# RK3562-VCCIO4.net
KiCad netlist of a schematic drawn in Altium Designer
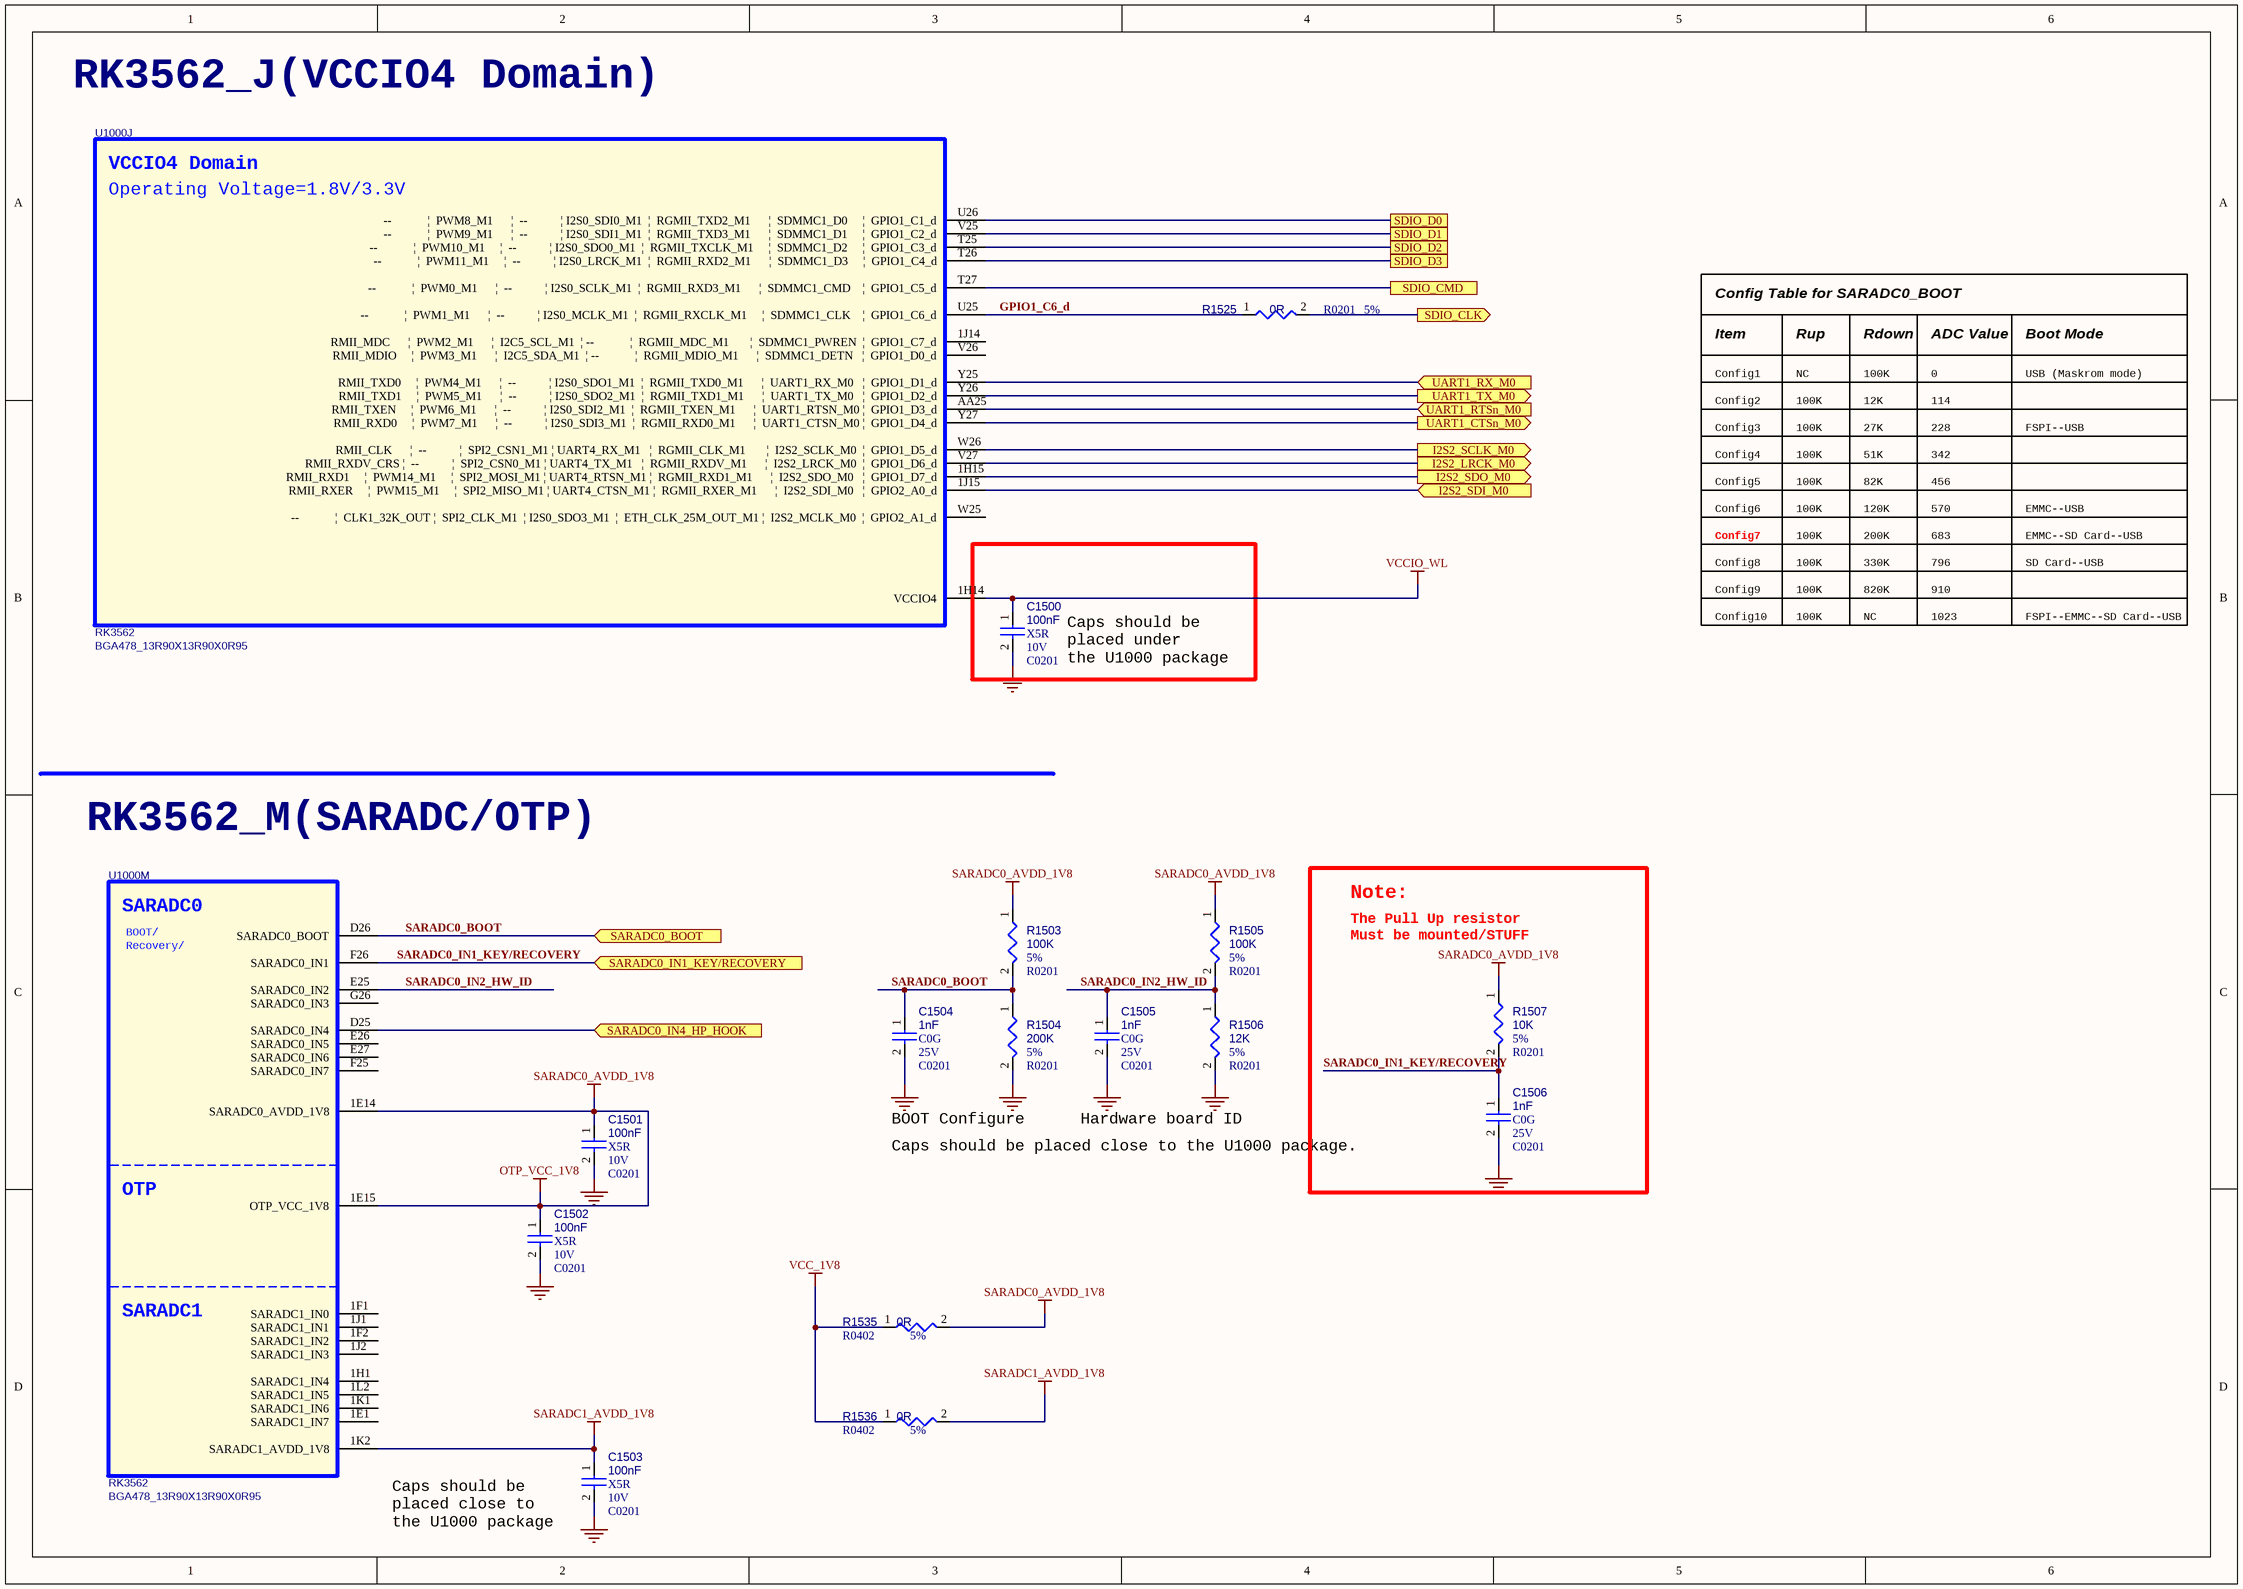
[diagram p0: RK3562-VCCIO4.SchDoc]

(export (version "E")
  (design (tool "Eeschema 10.0.6"))
  (components
    (comp (ref "C1500")
      (value "100nF")
      (footprint "C0201")
      (description "cap,100.00nF,+/-10%,10V,X5R,C0201")
      (fields
        (field (name "DIELECTRIC") "X5R")
        (field (name "PCB FOOTPRINT") "C0201")
        (field (name "VOLTAGE") "10V")
        (field (name "TOLERANCE") "10%")
        (field (name "MANUFACTURER") "TDK")
        (field (name "CREATED BY") "JJJ")
      )
      (libsource (lib "RK3562_REF") (part "CAP NP"))
    )
    (comp (ref "C1501")
      (value "100nF")
      (footprint "C0201")
      (description "cap,100.00nF,+/-10%,10V,X5R,C0201")
      (fields
        (field (name "DIELECTRIC") "X5R")
        (field (name "PCB FOOTPRINT") "C0201")
        (field (name "VOLTAGE") "10V")
        (field (name "TOLERANCE") "10%")
        (field (name "MANUFACTURER") "TDK")
        (field (name "CREATED BY") "JJJ")
      )
      (libsource (lib "RK3562_REF") (part "CAP NP"))
    )
    (comp (ref "C1502")
      (value "100nF")
      (footprint "C0201")
      (description "cap,100.00nF,+/-10%,10V,X5R,C0201")
      (fields
        (field (name "DIELECTRIC") "X5R")
        (field (name "PCB FOOTPRINT") "C0201")
        (field (name "VOLTAGE") "10V")
        (field (name "MANUFACTURER") "TDK")
        (field (name "TOLERANCE") "10%")
        (field (name "CREATED BY") "JJJ")
      )
      (libsource (lib "RK3562_REF") (part "CAP NP"))
    )
    (comp (ref "C1503")
      (value "100nF")
      (footprint "C0201")
      (description "cap,100.00nF,+/-10%,10V,X5R,C0201")
      (fields
        (field (name "DIELECTRIC") "X5R")
        (field (name "PCB FOOTPRINT") "C0201")
        (field (name "VOLTAGE") "10V")
        (field (name "TOLERANCE") "10%")
        (field (name "MANUFACTURER") "TDK")
        (field (name "CREATED BY") "JJJ")
      )
      (libsource (lib "RK3562_REF") (part "CAP NP"))
    )
    (comp (ref "C1504")
      (value "1nF")
      (footprint "C0201")
      (description "一般用片状陶瓷电容(GRM),cap,1nF,±5%,25V,C0G,C0201")
      (fields
        (field (name "DIELECTRIC") "C0G")
        (field (name "PCB FOOTPRINT") "C0201")
        (field (name "VOLTAGE") "25V")
        (field (name "MANUFACTURER") "murata")
        (field (name "TOLERANCE") "±5%")
        (field (name "CREATED BY") "JJJ")
      )
      (libsource (lib "RK3562_REF") (part "CAP NP"))
    )
    (comp (ref "C1505")
      (value "1nF")
      (footprint "C0201")
      (description "一般用片状陶瓷电容(GRM),cap,1nF,±5%,25V,C0G,C0201")
      (fields
        (field (name "DIELECTRIC") "C0G")
        (field (name "PCB FOOTPRINT") "C0201")
        (field (name "VOLTAGE") "25V")
        (field (name "TOLERANCE") "±5%")
        (field (name "MANUFACTURER") "murata")
        (field (name "CREATED BY") "JJJ")
      )
      (libsource (lib "RK3562_REF") (part "CAP NP"))
    )
    (comp (ref "C1506")
      (value "1nF")
      (footprint "C0201")
      (description "一般用片状陶瓷电容(GRM),cap,1nF,±5%,25V,C0G,C0201")
      (fields
        (field (name "DIELECTRIC") "C0G")
        (field (name "PCB FOOTPRINT") "C0201")
        (field (name "VOLTAGE") "25V")
        (field (name "TOLERANCE") "±5%")
        (field (name "MANUFACTURER") "murata")
        (field (name "CREATED BY") "JJJ")
      )
      (libsource (lib "RK3562_REF") (part "CAP NP"))
    )
    (comp (ref "R1503")
      (value "100K")
      (footprint "R0201")
      (description "通用厚膜电阻,100K,+/-5%,R0201,1/20W.")
      (fields
        (field (name "TOLERANCE") "5%")
        (field (name "PCB FOOTPRINT") "R0201")
        (field (name "MANUFACTURER") "YAGEO")
        (field (name "CREATED BY") "YTL")
      )
      (libsource (lib "RK3562_REF") (part "RESISTOR"))
    )
    (comp (ref "R1504")
      (value "200K")
      (footprint "R0201")
      (description "通用厚膜电阻,200K,+/-5%,R0201,1/20W.")
      (fields
        (field (name "TOLERANCE") "5%")
        (field (name "PCB FOOTPRINT") "R0201")
        (field (name "MANUFACTURER") "YAGEO")
        (field (name "CREATED BY") "YTL")
      )
      (libsource (lib "RK3562_REF") (part "RESISTOR"))
    )
    (comp (ref "R1505")
      (value "100K")
      (footprint "R0201")
      (description "通用厚膜电阻,100K,+/-5%,R0201,1/20W.")
      (fields
        (field (name "TOLERANCE") "5%")
        (field (name "PCB FOOTPRINT") "R0201")
        (field (name "MANUFACTURER") "YAGEO")
        (field (name "CREATED BY") "YTL")
      )
      (libsource (lib "RK3562_REF") (part "RESISTOR"))
    )
    (comp (ref "R1506")
      (value "12K")
      (footprint "R0201")
      (description "通用厚膜电阻,12K,+/-5%,R0201,1/20W.")
      (fields
        (field (name "TOLERANCE") "5%")
        (field (name "PCB FOOTPRINT") "R0201")
        (field (name "MANUFACTURER") "YAGEO")
        (field (name "CREATED BY") "YTL")
      )
      (libsource (lib "RK3562_REF") (part "RESISTOR"))
    )
    (comp (ref "R1507")
      (value "10K")
      (footprint "R0201")
      (description "通用厚膜电阻,10K,+/-5%,R0201,1/20W.")
      (fields
        (field (name "TOLERANCE") "5%")
        (field (name "PCB FOOTPRINT") "R0201")
        (field (name "MANUFACTURER") "YAGEO")
        (field (name "CREATED BY") "YTL")
      )
      (libsource (lib "RK3562_REF") (part "RESISTOR"))
    )
    (comp (ref "R1525")
      (value "0R")
      (footprint "R0201")
      (description "通用厚膜电阻,0R,+/-5%,R0201,1/20W.")
      (fields
        (field (name "TOLERANCE") "5%")
        (field (name "PCB FOOTPRINT") "R0201")
        (field (name "MANUFACTURER") "YAGEO")
        (field (name "CREATED BY") "YTL")
      )
      (libsource (lib "RK3562_REF") (part "RESISTOR"))
    )
    (comp (ref "R1535")
      (value "0R")
      (footprint "R0402")
      (description "通用厚膜电阻,0R,+/-5%,R0402,1/16W.")
      (fields
        (field (name "TOLERANCE") "5%")
        (field (name "PCB FOOTPRINT") "R0402")
        (field (name "MANUFACTURER") "YAGEO")
        (field (name "CREATED BY") "YTL")
      )
      (libsource (lib "RK3562_REF") (part "RESISTOR"))
    )
    (comp (ref "R1536")
      (value "0R")
      (footprint "R0402")
      (description "通用厚膜电阻,0R,+/-5%,R0402,1/16W.")
      (fields
        (field (name "TOLERANCE") "5%")
        (field (name "PCB FOOTPRINT") "R0402")
        (field (name "MANUFACTURER") "YAGEO")
        (field (name "CREATED BY") "YTL")
      )
      (libsource (lib "RK3562_REF") (part "RESISTOR"))
    )
    (comp (ref "U1000")
      (value "RK3562")
      (footprint "BGA478_13R90X13R90X0R95")
      (description "ROCKCHIP SOC")
      (fields
        (field (name "PCB FOOTPRINT") "BGA478_13R90X13R90X0R95")
        (field (name "MANUFACTURER") "Rockchip (瑞芯微)")
        (field (name "CREATED BY") "JJJ")
      )
      (libsource (lib "RK3562_REF") (part "SOC_RK3562"))
    )
  )
  (nets
    (net (code "1") (name "/GPIO1_C6_d") (class "Default")
      (node (ref "R1525") (pin "1") (pinfunction "1_1") (pintype "passive"))
      (node (ref "U1000") (pin "U25") (pinfunction "--____________¦__PWM1_M1______¦__--___________¦_I2S0_MCLK_M1__¦__RGMII_RXCLK_M1_____¦__SDMMC1_CLK____¦__GPIO1_C6_d_U25") (pintype "passive"))
    )
    (net (code "2") (name "/I2S2_LRCK_M0") (class "Default")
      (node (ref "U1000") (pin "V27") (pinfunction "RMII_RXDV_CRS_¦__--___________¦__SPI2_CSN0_M1_¦_UART4_TX_M1___¦__RGMII_RXDV_M1______¦__I2S2_LRCK_M0__¦__GPIO1_D6_d_V27") (pintype "passive"))
    )
    (net (code "3") (name "/I2S2_SCLK_M0") (class "Default")
      (node (ref "U1000") (pin "W26") (pinfunction "RMII_CLK______¦__--___________¦__SPI2_CSN1_M1_¦_UART4_RX_M1___¦__RGMII_CLK_M1_______¦__I2S2_SCLK_M0__¦__GPIO1_D5_d_W26") (pintype "passive"))
    )
    (net (code "4") (name "/I2S2_SDI_M0") (class "Default")
      (node (ref "U1000") (pin "1J15") (pinfunction "RMII_RXER_____¦__PWM15_M1_____¦__SPI2_MISO_M1_¦_UART4_CTSN_M1_¦__RGMII_RXER_M1______¦__I2S2_SDI_M0___¦__GPIO2_A0_d_1J15") (pintype "passive"))
    )
    (net (code "5") (name "/I2S2_SDO_M0") (class "Default")
      (node (ref "U1000") (pin "1H15") (pinfunction "RMII_RXD1_____¦__PWM14_M1_____¦__SPI2_MOSI_M1_¦_UART4_RTSN_M1_¦__RGMII_RXD1_M1______¦__I2S2_SDO_M0___¦__GPIO1_D7_d_1H15") (pintype "passive"))
    )
    (net (code "6") (name "/SARADC0_BOOT") (class "Default")
      (node (ref "C1504") (pin "1") (pinfunction "1_1") (pintype "passive"))
      (node (ref "R1503") (pin "2") (pinfunction "2_2") (pintype "passive"))
      (node (ref "R1504") (pin "1") (pinfunction "1_1") (pintype "passive"))
      (node (ref "U1000") (pin "D26") (pinfunction "SARADC0_BOOT_D26") (pintype "passive"))
    )
    (net (code "7") (name "/SARADC0_IN1_KEY{slash}RECOVERY") (class "Default")
      (node (ref "C1506") (pin "1") (pinfunction "1_1") (pintype "passive"))
      (node (ref "R1507") (pin "2") (pinfunction "2_2") (pintype "passive"))
      (node (ref "U1000") (pin "F26") (pinfunction "SARADC0_IN1_F26") (pintype "passive"))
    )
    (net (code "8") (name "/SARADC0_IN2_HW_ID") (class "Default")
      (node (ref "C1505") (pin "1") (pinfunction "1_1") (pintype "passive"))
      (node (ref "R1505") (pin "2") (pinfunction "2_2") (pintype "passive"))
      (node (ref "R1506") (pin "1") (pinfunction "1_1") (pintype "passive"))
      (node (ref "U1000") (pin "E25") (pinfunction "SARADC0_IN2_E25") (pintype "passive"))
    )
    (net (code "9") (name "/SARADC0_IN4_HP_HOOK") (class "Default")
      (node (ref "U1000") (pin "D25") (pinfunction "SARADC0_IN4_D25") (pintype "passive"))
    )
    (net (code "10") (name "/SDIO_CLK") (class "Default")
      (node (ref "R1525") (pin "2") (pinfunction "2_2") (pintype "passive"))
    )
    (net (code "11") (name "/SDIO_CMD") (class "Default")
      (node (ref "U1000") (pin "T27") (pinfunction "--____________¦__PWM0_M1______¦__--___________¦_I2S0_SCLK_M1__¦__RGMII_RXD3_M1______¦__SDMMC1_CMD____¦__GPIO1_C5_d_T27") (pintype "passive"))
    )
    (net (code "12") (name "/SDIO_D0") (class "Default")
      (node (ref "U1000") (pin "U26") (pinfunction "--____________¦__PWM8_M1______¦__--___________¦_I2S0_SDI0_M1__¦__RGMII_TXD2_M1______¦__SDMMC1_D0_____¦__GPIO1_C1_d_U26") (pintype "passive"))
    )
    (net (code "13") (name "/SDIO_D1") (class "Default")
      (node (ref "U1000") (pin "V25") (pinfunction "--____________¦__PWM9_M1______¦__--___________¦_I2S0_SDI1_M1__¦__RGMII_TXD3_M1______¦__SDMMC1_D1_____¦__GPIO1_C2_d_V25") (pintype "passive"))
    )
    (net (code "14") (name "/SDIO_D2") (class "Default")
      (node (ref "U1000") (pin "T25") (pinfunction "--____________¦__PWM10_M1_____¦__--___________¦_I2S0_SDO0_M1__¦__RGMII_TXCLK_M1_____¦__SDMMC1_D2_____¦__GPIO1_C3_d_T25") (pintype "passive"))
    )
    (net (code "15") (name "/SDIO_D3") (class "Default")
      (node (ref "U1000") (pin "T26") (pinfunction "--____________¦__PWM11_M1_____¦__--___________¦_I2S0_LRCK_M1__¦__RGMII_RXD2_M1______¦__SDMMC1_D3_____¦__GPIO1_C4_d_T26") (pintype "passive"))
    )
    (net (code "16") (name "/UART1_CTSn_M0") (class "Default")
      (node (ref "U1000") (pin "Y27") (pinfunction "RMII_RXD0_____¦__PWM7_M1______¦__--___________¦_I2S0_SDI3_M1__¦__RGMII_RXD0_M1______¦__UART1_CTSN_M0_¦__GPIO1_D4_d_Y27") (pintype "passive"))
    )
    (net (code "17") (name "/UART1_RTSn_M0") (class "Default")
      (node (ref "U1000") (pin "AA25") (pinfunction "RMII_TXEN_____¦__PWM6_M1______¦__--___________¦_I2S0_SDI2_M1__¦__RGMII_TXEN_M1______¦__UART1_RTSN_M0_¦__GPIO1_D3_d_AA25") (pintype "passive"))
    )
    (net (code "18") (name "/UART1_RX_M0") (class "Default")
      (node (ref "U1000") (pin "Y25") (pinfunction "RMII_TXD0_____¦__PWM4_M1______¦__--___________¦_I2S0_SDO1_M1__¦__RGMII_TXD0_M1______¦__UART1_RX_M0___¦__GPIO1_D1_d_Y25") (pintype "passive"))
    )
    (net (code "19") (name "/UART1_TX_M0") (class "Default")
      (node (ref "U1000") (pin "Y26") (pinfunction "RMII_TXD1_____¦__PWM5_M1______¦__--___________¦_I2S0_SDO2_M1__¦__RGMII_TXD1_M1______¦__UART1_TX_M0___¦__GPIO1_D2_d_Y26") (pintype "passive"))
    )
    (net (code "20") (name "GND") (class "Default")
      (node (ref "C1500") (pin "2") (pinfunction "2_2") (pintype "passive"))
      (node (ref "C1501") (pin "2") (pinfunction "2_2") (pintype "passive"))
      (node (ref "C1502") (pin "2") (pinfunction "2_2") (pintype "passive"))
      (node (ref "C1503") (pin "2") (pinfunction "2_2") (pintype "passive"))
      (node (ref "C1504") (pin "2") (pinfunction "2_2") (pintype "passive"))
      (node (ref "C1505") (pin "2") (pinfunction "2_2") (pintype "passive"))
      (node (ref "C1506") (pin "2") (pinfunction "2_2") (pintype "passive"))
      (node (ref "R1504") (pin "2") (pinfunction "2_2") (pintype "passive"))
      (node (ref "R1506") (pin "2") (pinfunction "2_2") (pintype "passive"))
    )
    (net (code "21") (name "OTP_VCC_1V8") (class "Default")
      (node (ref "C1501") (pin "1") (pinfunction "1_1") (pintype "passive"))
      (node (ref "C1502") (pin "1") (pinfunction "1_1") (pintype "passive"))
      (node (ref "R1503") (pin "1") (pinfunction "1_1") (pintype "passive"))
      (node (ref "R1505") (pin "1") (pinfunction "1_1") (pintype "passive"))
      (node (ref "R1507") (pin "1") (pinfunction "1_1") (pintype "passive"))
      (node (ref "R1535") (pin "2") (pinfunction "2_2") (pintype "passive"))
      (node (ref "U1000") (pin "1E14") (pinfunction "SARADC0_AVDD_1V8_1E14") (pintype "passive"))
      (node (ref "U1000") (pin "1E15") (pinfunction "OTP_VCC_1V8_1E15") (pintype "passive"))
    )
    (net (code "22") (name "SARADC1_AVDD_1V8") (class "Default")
      (node (ref "C1503") (pin "1") (pinfunction "1_1") (pintype "passive"))
      (node (ref "R1536") (pin "2") (pinfunction "2_2") (pintype "passive"))
      (node (ref "U1000") (pin "1K2") (pinfunction "SARADC1_AVDD_1V8_1K2") (pintype "passive"))
    )
    (net (code "23") (name "VCCIO_WL") (class "Default")
      (node (ref "C1500") (pin "1") (pinfunction "1_1") (pintype "passive"))
      (node (ref "U1000") (pin "1H14") (pinfunction "VCCIO4_1H14") (pintype "passive"))
    )
    (net (code "24") (name "VCC_1V8") (class "Default")
      (node (ref "R1535") (pin "1") (pinfunction "1_1") (pintype "passive"))
      (node (ref "R1536") (pin "1") (pinfunction "1_1") (pintype "passive"))
    )
    (net (code "25") (name "unconnected-(U1000J---____________¦__CLK1_32K_OUT_¦__SPI2_CLK_M1__¦_I2S0_SDO3_M1__¦__ETH_CLK_25M_OUT_M1_¦__I2S2_MCLK_M0__¦__GPIO2_A1_d-PadW25)") (class "Default")
      (node (ref "U1000") (pin "W25") (pinfunction "--____________¦__CLK1_32K_OUT_¦__SPI2_CLK_M1__¦_I2S0_SDO3_M1__¦__ETH_CLK_25M_OUT_M1_¦__I2S2_MCLK_M0__¦__GPIO2_A1_d_W25") (pintype "passive"))
    )
    (net (code "26") (name "unconnected-(U1000J-RMII_MDC______¦__PWM2_M1______¦__I2C5_SCL_M1__¦_--____________¦__RGMII_MDC_M1_______¦__SDMMC1_PWREN__¦__GPIO1_C7_d-Pad1J14)") (class "Default")
      (node (ref "U1000") (pin "1J14") (pinfunction "RMII_MDC______¦__PWM2_M1______¦__I2C5_SCL_M1__¦_--____________¦__RGMII_MDC_M1_______¦__SDMMC1_PWREN__¦__GPIO1_C7_d_1J14") (pintype "passive"))
    )
    (net (code "27") (name "unconnected-(U1000J-RMII_MDIO_____¦__PWM3_M1______¦__I2C5_SDA_M1__¦_--____________¦__RGMII_MDIO_M1______¦__SDMMC1_DETN___¦__GPIO1_D0_d-PadV26)") (class "Default")
      (node (ref "U1000") (pin "V26") (pinfunction "RMII_MDIO_____¦__PWM3_M1______¦__I2C5_SDA_M1__¦_--____________¦__RGMII_MDIO_M1______¦__SDMMC1_DETN___¦__GPIO1_D0_d_V26") (pintype "passive"))
    )
    (net (code "28") (name "unconnected-(U1000M-SARADC0_IN3-PadG26)") (class "Default")
      (node (ref "U1000") (pin "G26") (pinfunction "SARADC0_IN3_G26") (pintype "passive"))
    )
    (net (code "29") (name "unconnected-(U1000M-SARADC0_IN5-PadE26)") (class "Default")
      (node (ref "U1000") (pin "E26") (pinfunction "SARADC0_IN5_E26") (pintype "passive"))
    )
    (net (code "30") (name "unconnected-(U1000M-SARADC0_IN6-PadE27)") (class "Default")
      (node (ref "U1000") (pin "E27") (pinfunction "SARADC0_IN6_E27") (pintype "passive"))
    )
    (net (code "31") (name "unconnected-(U1000M-SARADC0_IN7-PadF25)") (class "Default")
      (node (ref "U1000") (pin "F25") (pinfunction "SARADC0_IN7_F25") (pintype "passive"))
    )
    (net (code "32") (name "unconnected-(U1000M-SARADC1_IN0-Pad1F1)") (class "Default")
      (node (ref "U1000") (pin "1F1") (pinfunction "SARADC1_IN0_1F1") (pintype "passive"))
    )
    (net (code "33") (name "unconnected-(U1000M-SARADC1_IN1-Pad1J1)") (class "Default")
      (node (ref "U1000") (pin "1J1") (pinfunction "SARADC1_IN1_1J1") (pintype "passive"))
    )
    (net (code "34") (name "unconnected-(U1000M-SARADC1_IN2-Pad1F2)") (class "Default")
      (node (ref "U1000") (pin "1F2") (pinfunction "SARADC1_IN2_1F2") (pintype "passive"))
    )
    (net (code "35") (name "unconnected-(U1000M-SARADC1_IN3-Pad1J2)") (class "Default")
      (node (ref "U1000") (pin "1J2") (pinfunction "SARADC1_IN3_1J2") (pintype "passive"))
    )
    (net (code "36") (name "unconnected-(U1000M-SARADC1_IN4-Pad1H1)") (class "Default")
      (node (ref "U1000") (pin "1H1") (pinfunction "SARADC1_IN4_1H1") (pintype "passive"))
    )
    (net (code "37") (name "unconnected-(U1000M-SARADC1_IN5-Pad1L2)") (class "Default")
      (node (ref "U1000") (pin "1L2") (pinfunction "SARADC1_IN5_1L2") (pintype "passive"))
    )
    (net (code "38") (name "unconnected-(U1000M-SARADC1_IN6-Pad1K1)") (class "Default")
      (node (ref "U1000") (pin "1K1") (pinfunction "SARADC1_IN6_1K1") (pintype "passive"))
    )
    (net (code "39") (name "unconnected-(U1000M-SARADC1_IN7-Pad1E1)") (class "Default")
      (node (ref "U1000") (pin "1E1") (pinfunction "SARADC1_IN7_1E1") (pintype "passive"))
    )
  )
)
